# DAC_VGA_8b.net
KiCad netlist of a schematic drawn in EAGLE
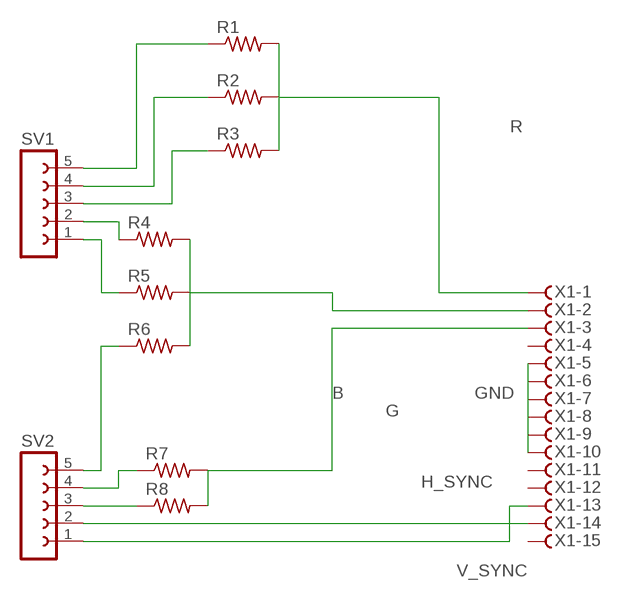
[diagram p0: schematic, sheet 1]

(export (version "E")
  (design (tool "Eeschema 10.0.6"))
  (components
    (comp (ref "R1")
      (value "R-US_0204/5")
      (footprint "eagle-import:0204_5")
      (libsource (lib "eagle-import") (part "R-US_0204/5"))
    )
    (comp (ref "R2")
      (value "R-US_0204/5")
      (footprint "eagle-import:0204_5")
      (libsource (lib "eagle-import") (part "R-US_0204/5"))
    )
    (comp (ref "R3")
      (value "R-US_0204/5")
      (footprint "eagle-import:0204_5")
      (libsource (lib "eagle-import") (part "R-US_0204/5"))
    )
    (comp (ref "R4")
      (value "R-US_0204/5")
      (footprint "eagle-import:0204_5")
      (libsource (lib "eagle-import") (part "R-US_0204/5"))
    )
    (comp (ref "R5")
      (value "R-US_0204/5")
      (footprint "eagle-import:0204_5")
      (libsource (lib "eagle-import") (part "R-US_0204/5"))
    )
    (comp (ref "R6")
      (value "R-US_0204/5")
      (footprint "eagle-import:0204_5")
      (libsource (lib "eagle-import") (part "R-US_0204/5"))
    )
    (comp (ref "R7")
      (value "R-US_0204/5")
      (footprint "eagle-import:0204_5")
      (libsource (lib "eagle-import") (part "R-US_0204/5"))
    )
    (comp (ref "R8")
      (value "R-US_0204/5")
      (footprint "eagle-import:0204_5")
      (libsource (lib "eagle-import") (part "R-US_0204/5"))
    )
    (comp (ref "SV1")
      (value "FE05W")
      (footprint "eagle-import:FE05W")
      (libsource (lib "eagle-import") (part "FE05W"))
    )
    (comp (ref "SV2")
      (value "FE05W")
      (footprint "eagle-import:FE05W")
      (libsource (lib "eagle-import") (part "FE05W"))
    )
    (comp (ref "X1")
      (value "HF15VS")
      (footprint "eagle-import:HDF15V")
      (libsource (lib "eagle-import") (part "HF15?SV"))
    )
  )
  (nets
    (net (code "1") (name "/B") (class "Default")
      (node (ref "R7") (pin "2") (pinfunction "2_2") (pintype "passive"))
      (node (ref "R8") (pin "2") (pinfunction "2_2") (pintype "passive"))
      (node (ref "X1") (pin "3") (pinfunction "F_3") (pintype "passive"))
    )
    (net (code "2") (name "/G") (class "Default")
      (node (ref "R4") (pin "2") (pinfunction "2_2") (pintype "passive"))
      (node (ref "R5") (pin "2") (pinfunction "2_2") (pintype "passive"))
      (node (ref "R6") (pin "2") (pinfunction "2_2") (pintype "passive"))
      (node (ref "X1") (pin "2") (pinfunction "F_2") (pintype "passive"))
    )
    (net (code "3") (name "/GND") (class "Default")
      (node (ref "X1") (pin "10") (pinfunction "F_10") (pintype "passive"))
      (node (ref "X1") (pin "5") (pinfunction "F_5") (pintype "passive"))
      (node (ref "X1") (pin "6") (pinfunction "F_6") (pintype "passive"))
      (node (ref "X1") (pin "7") (pinfunction "F_7") (pintype "passive"))
      (node (ref "X1") (pin "8") (pinfunction "F_8") (pintype "passive"))
      (node (ref "X1") (pin "9") (pinfunction "F_9") (pintype "passive"))
    )
    (net (code "4") (name "/H_SYNC") (class "Default")
      (node (ref "SV2") (pin "2") (pinfunction "2_2") (pintype "passive"))
      (node (ref "X1") (pin "14") (pinfunction "F_14") (pintype "passive"))
    )
    (net (code "5") (name "/R") (class "Default")
      (node (ref "R1") (pin "2") (pinfunction "2_2") (pintype "passive"))
      (node (ref "R2") (pin "2") (pinfunction "2_2") (pintype "passive"))
      (node (ref "R3") (pin "2") (pinfunction "2_2") (pintype "passive"))
      (node (ref "X1") (pin "1") (pinfunction "F_1") (pintype "passive"))
    )
    (net (code "6") (name "/V_SYNC") (class "Default")
      (node (ref "SV2") (pin "1") (pinfunction "1_1") (pintype "passive"))
      (node (ref "X1") (pin "13") (pinfunction "F_13") (pintype "passive"))
    )
    (net (code "7") (name "Net-(R1-Pad1)") (class "Default")
      (node (ref "R1") (pin "1") (pinfunction "1_1") (pintype "passive"))
      (node (ref "SV1") (pin "5") (pinfunction "5_5") (pintype "passive"))
    )
    (net (code "8") (name "Net-(R2-Pad1)") (class "Default")
      (node (ref "R2") (pin "1") (pinfunction "1_1") (pintype "passive"))
      (node (ref "SV1") (pin "4") (pinfunction "4_4") (pintype "passive"))
    )
    (net (code "9") (name "Net-(R3-Pad1)") (class "Default")
      (node (ref "R3") (pin "1") (pinfunction "1_1") (pintype "passive"))
      (node (ref "SV1") (pin "3") (pinfunction "3_3") (pintype "passive"))
    )
    (net (code "10") (name "Net-(R4-Pad1)") (class "Default")
      (node (ref "R4") (pin "1") (pinfunction "1_1") (pintype "passive"))
      (node (ref "SV1") (pin "2") (pinfunction "2_2") (pintype "passive"))
    )
    (net (code "11") (name "Net-(R5-Pad1)") (class "Default")
      (node (ref "R5") (pin "1") (pinfunction "1_1") (pintype "passive"))
      (node (ref "SV1") (pin "1") (pinfunction "1_1") (pintype "passive"))
    )
    (net (code "12") (name "Net-(R6-Pad1)") (class "Default")
      (node (ref "R6") (pin "1") (pinfunction "1_1") (pintype "passive"))
      (node (ref "SV2") (pin "5") (pinfunction "5_5") (pintype "passive"))
    )
    (net (code "13") (name "Net-(R7-Pad1)") (class "Default")
      (node (ref "R7") (pin "1") (pinfunction "1_1") (pintype "passive"))
      (node (ref "SV2") (pin "4") (pinfunction "4_4") (pintype "passive"))
    )
    (net (code "14") (name "Net-(R8-Pad1)") (class "Default")
      (node (ref "R8") (pin "1") (pinfunction "1_1") (pintype "passive"))
      (node (ref "SV2") (pin "3") (pinfunction "3_3") (pintype "passive"))
    )
    (net (code "15") (name "unconnected-(X1C-F-Pad11)") (class "Default")
      (node (ref "X1") (pin "11") (pinfunction "F_11") (pintype "passive"))
    )
    (net (code "16") (name "unconnected-(X1D-F-Pad12)") (class "Default")
      (node (ref "X1") (pin "12") (pinfunction "F_12") (pintype "passive"))
    )
    (net (code "17") (name "unconnected-(X1G-F-Pad15)") (class "Default")
      (node (ref "X1") (pin "15") (pinfunction "F_15") (pintype "passive"))
    )
    (net (code "18") (name "unconnected-(X1J-F-Pad4)") (class "Default")
      (node (ref "X1") (pin "4") (pinfunction "F_4") (pintype "passive"))
    )
  )
)
